# FPSInterface.net
KiCad netlist of a schematic drawn in Altium Designer
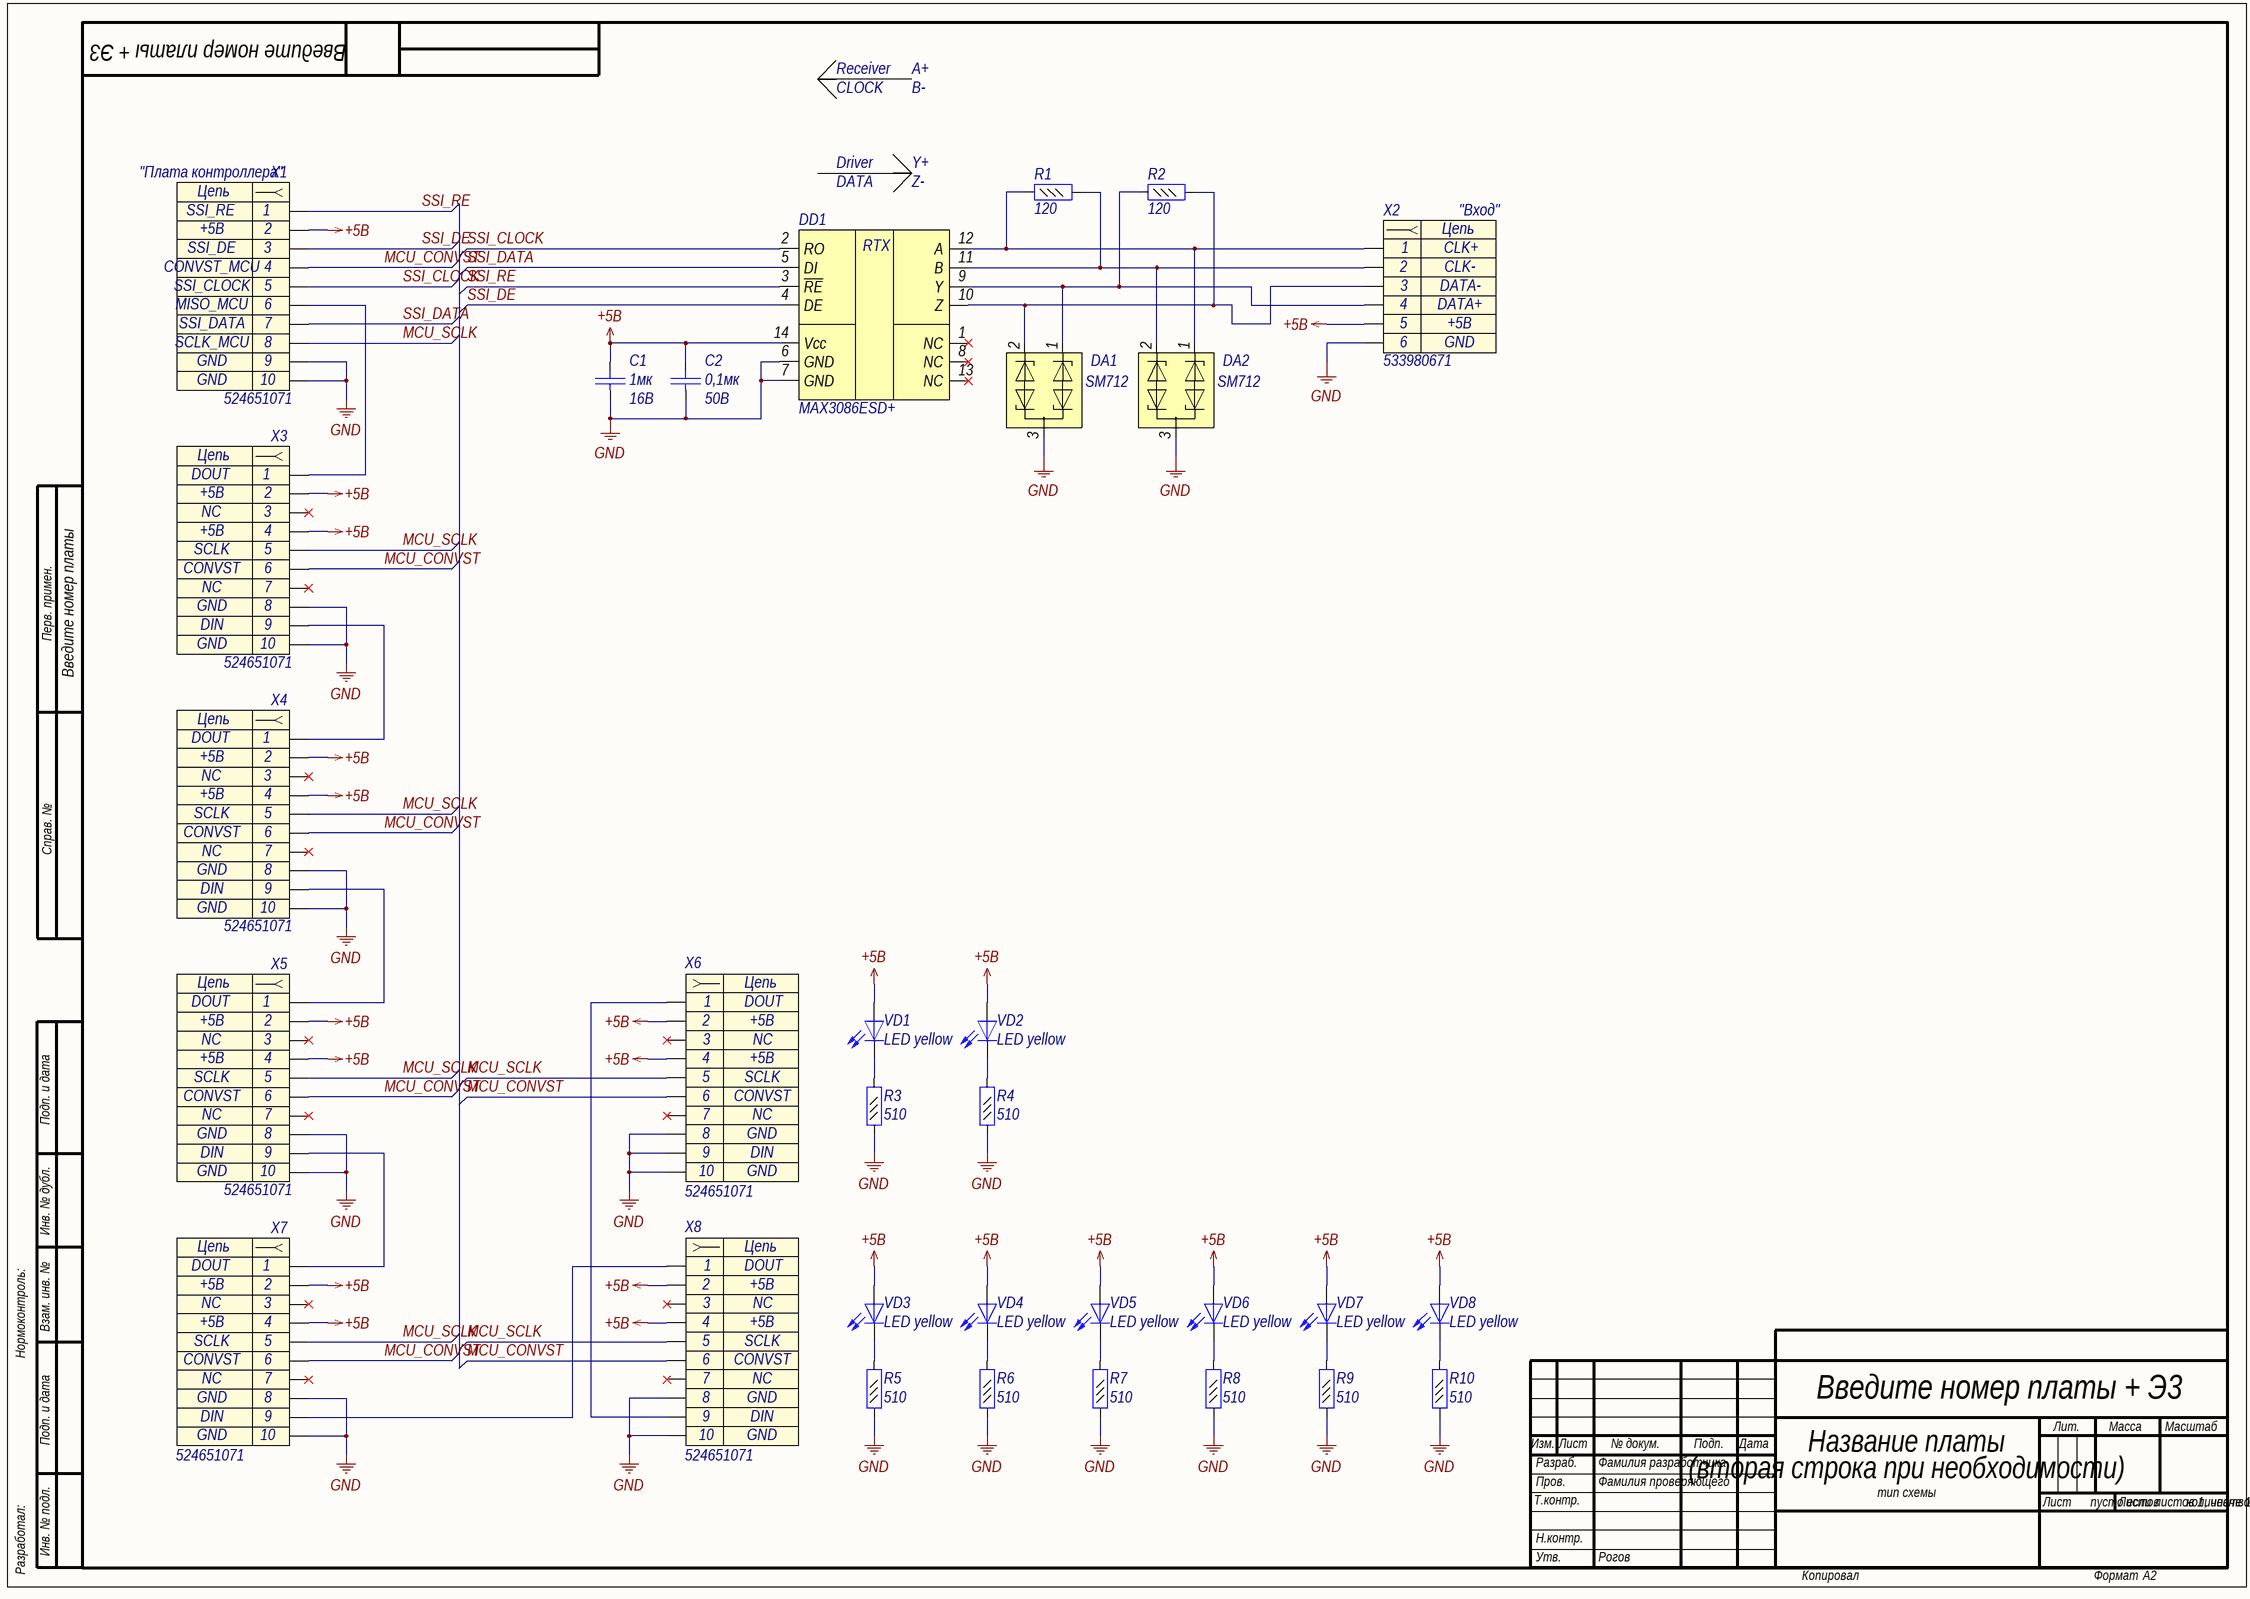
[diagram p0: FPSInterface.SchDoc]

(export (version "E")
  (design (tool "Eeschema 10.0.6"))
  (components
    (comp (ref "C1")
      (value "1мк")
      (footprint "C0603")
      (description "Конденсатор")
      (fields
        (field (name "VOLTAGE") "16B")
        (field (name "PART NUMBER") "GRM188R71C105KA12D**")
        (field (name "Comment") "Capacitor")
      )
      (libsource (lib "MOP44") (part "Capacitor"))
    )
    (comp (ref "C2")
      (value "0,1мк")
      (footprint "C0402")
      (description "Конденсатор")
      (fields
        (field (name "VOLTAGE") "50В")
        (field (name "PART NUMBER") "GRM155R71H104KE14D")
        (field (name "Comment") "Capacitor")
      )
      (libsource (lib "MOP44") (part "Capacitor"))
    )
    (comp (ref "DA1")
      (value "SM712")
      (footprint "SOT23-3")
      (description "TVS")
      (fields (field (name "PART NUMBER") "SM712.TCT"))
      (libsource (lib "MOP44") (part "SM712"))
    )
    (comp (ref "DA2")
      (value "SM712")
      (footprint "SOT23-3")
      (description "TVS")
      (fields (field (name "PART NUMBER") "SM712.TCT"))
      (libsource (lib "MOP44") (part "SM712"))
    )
    (comp (ref "DD1")
      (value "~")
      (footprint "SO14")
      (description "Fail-Safe, High-Speed (10Mbps),  Slew-Rate-Limited RS-485/RS-422 Transceivers")
      (fields (field (name "PART NUMBER") "MAX3086ESD+"))
      (libsource (lib "MOP44") (part "MAX3086"))
    )
    (comp (ref "R1")
      (value "120")
      (footprint "R0402")
      (description "Резистор")
      (fields (field (name "PART NUMBER") "RC0402FR-07120RL") (field (name "POWER") "0,062Вт"))
      (libsource (lib "") (part "Resistor_0,062Вт_1"))
    )
    (comp (ref "R2")
      (value "120")
      (footprint "R0402")
      (description "Резистор")
      (fields (field (name "PART NUMBER") "RC0402FR-07120RL") (field (name "POWER") "0,062Вт"))
      (libsource (lib "") (part "Resistor_0,062Вт_1"))
    )
    (comp (ref "R3")
      (value "510")
      (footprint "R0402")
      (description "Резистор")
      (fields (field (name "PART NUMBER") "RC0402FR-07510RL") (field (name "POWER") "0,062Вт"))
      (libsource (lib "MOP44") (part "Resistor_0,062Вт"))
    )
    (comp (ref "R4")
      (value "510")
      (footprint "R0402")
      (description "Резистор")
      (fields (field (name "PART NUMBER") "RC0402FR-07510RL") (field (name "POWER") "0,062Вт"))
      (libsource (lib "MOP44") (part "Resistor_0,062Вт"))
    )
    (comp (ref "R5")
      (value "510")
      (footprint "R0402")
      (description "Резистор")
      (fields (field (name "PART NUMBER") "RC0402FR-07510RL") (field (name "POWER") "0,062Вт"))
      (libsource (lib "MOP44") (part "Resistor_0,062Вт"))
    )
    (comp (ref "R6")
      (value "510")
      (footprint "R0402")
      (description "Резистор")
      (fields (field (name "PART NUMBER") "RC0402FR-07510RL") (field (name "POWER") "0,062Вт"))
      (libsource (lib "MOP44") (part "Resistor_0,062Вт"))
    )
    (comp (ref "R7")
      (value "510")
      (footprint "R0402")
      (description "Резистор")
      (fields (field (name "PART NUMBER") "RC0402FR-07510RL") (field (name "POWER") "0,062Вт"))
      (libsource (lib "MOP44") (part "Resistor_0,062Вт"))
    )
    (comp (ref "R8")
      (value "510")
      (footprint "R0402")
      (description "Резистор")
      (fields (field (name "PART NUMBER") "RC0402FR-07510RL") (field (name "POWER") "0,062Вт"))
      (libsource (lib "MOP44") (part "Resistor_0,062Вт"))
    )
    (comp (ref "R9")
      (value "510")
      (footprint "R0402")
      (description "Резистор")
      (fields (field (name "PART NUMBER") "RC0402FR-07510RL") (field (name "POWER") "0,062Вт"))
      (libsource (lib "MOP44") (part "Resistor_0,062Вт"))
    )
    (comp (ref "R10")
      (value "510")
      (footprint "R0402")
      (description "Резистор")
      (fields (field (name "PART NUMBER") "RC0402FR-07510RL") (field (name "POWER") "0,062Вт"))
      (libsource (lib "MOP44") (part "Resistor_0,062Вт"))
    )
    (comp (ref "VD1")
      (value "LED")
      (footprint "L_0402_YELLOW")
      (description "Светодиод")
      (fields (field (name "PART NAME") "LED yellow") (field (name "PART NUMBER") "KPHHS-1005SYCK"))
      (libsource (lib "MOP44") (part "LED"))
    )
    (comp (ref "VD2")
      (value "LED")
      (footprint "L_0402_YELLOW")
      (description "Светодиод")
      (fields (field (name "PART NAME") "LED yellow") (field (name "PART NUMBER") "KPHHS-1005SYCK"))
      (libsource (lib "MOP44") (part "LED"))
    )
    (comp (ref "VD3")
      (value "LED")
      (footprint "L_0402_YELLOW")
      (description "Светодиод")
      (fields (field (name "PART NAME") "LED yellow") (field (name "PART NUMBER") "KPHHS-1005SYCK"))
      (libsource (lib "MOP44") (part "LED"))
    )
    (comp (ref "VD4")
      (value "LED")
      (footprint "L_0402_YELLOW")
      (description "Светодиод")
      (fields (field (name "PART NAME") "LED yellow") (field (name "PART NUMBER") "KPHHS-1005SYCK"))
      (libsource (lib "MOP44") (part "LED"))
    )
    (comp (ref "VD5")
      (value "LED")
      (footprint "L_0402_YELLOW")
      (description "Светодиод")
      (fields (field (name "PART NAME") "LED yellow") (field (name "PART NUMBER") "KPHHS-1005SYCK"))
      (libsource (lib "MOP44") (part "LED"))
    )
    (comp (ref "VD6")
      (value "LED")
      (footprint "L_0402_YELLOW")
      (description "Светодиод")
      (fields (field (name "PART NAME") "LED yellow") (field (name "PART NUMBER") "KPHHS-1005SYCK"))
      (libsource (lib "MOP44") (part "LED"))
    )
    (comp (ref "VD7")
      (value "LED")
      (footprint "L_0402_YELLOW")
      (description "Светодиод")
      (fields (field (name "PART NAME") "LED yellow") (field (name "PART NUMBER") "KPHHS-1005SYCK"))
      (libsource (lib "MOP44") (part "LED"))
    )
    (comp (ref "VD8")
      (value "LED")
      (footprint "L_0402_YELLOW")
      (description "Светодиод")
      (fields (field (name "PART NAME") "LED yellow") (field (name "PART NUMBER") "KPHHS-1005SYCK"))
      (libsource (lib "MOP44") (part "LED"))
    )
    (comp (ref "X1")
      (value "\"Плата контроллера\"")
      (footprint "SlimStack-10pin-vert-sct")
      (description "Разъем - 10 конт. розетка")
      (fields (field (name "PART NUMBER") "524651071"))
      (libsource (lib "") (part "Header_10_sct_1"))
    )
    (comp (ref "X2")
      (value "\"Вход\"")
      (footprint "MOLEX_533980671")
      (description "Разъем - 6 конт. розетка")
      (fields (field (name "PART NUMBER") "533980671"))
      (libsource (lib "MOP44") (part "Header_6_sct"))
    )
    (comp (ref "X3")
      (value "Header_10_sct")
      (footprint "SlimStack-10pin-vert-sct")
      (description "Разъем - 10 конт. розетка")
      (fields (field (name "PART NUMBER") "524651071"))
      (libsource (lib "") (part "Header_10_sct_1"))
    )
    (comp (ref "X4")
      (value "Header_10_sct")
      (footprint "SlimStack-10pin-vert-sct")
      (description "Разъем - 10 конт. розетка")
      (fields (field (name "PART NUMBER") "524651071"))
      (libsource (lib "") (part "Header_10_sct_1"))
    )
    (comp (ref "X5")
      (value "Header_10_sct")
      (footprint "SlimStack-10pin-vert-sct")
      (description "Разъем - 10 конт. розетка")
      (fields (field (name "PART NUMBER") "524651071"))
      (libsource (lib "") (part "Header_10_sct_1"))
    )
    (comp (ref "X6")
      (value "Header_10_sct")
      (footprint "SlimStack-10pin-vert-sct")
      (description "Разъем - 10 конт. розетка")
      (fields (field (name "PART NUMBER") "524651071"))
      (libsource (lib "MOP44") (part "Header_10_sct"))
    )
    (comp (ref "X7")
      (value "Header_10_sct")
      (footprint "SlimStack-10pin-vert-sct")
      (description "Разъем - 10 конт. розетка")
      (fields (field (name "PART NUMBER") "524651071"))
      (libsource (lib "") (part "Header_10_sct_1"))
    )
    (comp (ref "X8")
      (value "Header_10_sct")
      (footprint "SlimStack-10pin-vert-sct")
      (description "Разъем - 10 конт. розетка")
      (fields (field (name "PART NUMBER") "524651071"))
      (libsource (lib "MOP44") (part "Header_10_sct"))
    )
  )
  (nets
    (net (code "1") (name "+5B") (class "Default")
      (node (ref "C1") (pin "2") (pinfunction "2_2") (pintype "passive"))
      (node (ref "C2") (pin "2") (pinfunction "2_2") (pintype "passive"))
      (node (ref "DD1") (pin "14") (pinfunction "Vcc_14") (pintype "passive"))
      (node (ref "VD1") (pin "2") (pinfunction "A_2") (pintype "passive"))
      (node (ref "VD2") (pin "2") (pinfunction "A_2") (pintype "passive"))
      (node (ref "VD3") (pin "2") (pinfunction "A_2") (pintype "passive"))
      (node (ref "VD4") (pin "2") (pinfunction "A_2") (pintype "passive"))
      (node (ref "VD5") (pin "2") (pinfunction "A_2") (pintype "passive"))
      (node (ref "VD6") (pin "2") (pinfunction "A_2") (pintype "passive"))
      (node (ref "VD7") (pin "2") (pinfunction "A_2") (pintype "passive"))
      (node (ref "VD8") (pin "2") (pinfunction "A_2") (pintype "passive"))
      (node (ref "X1") (pin "2") (pinfunction "2_2") (pintype "passive"))
      (node (ref "X2") (pin "5") (pinfunction "5_5") (pintype "passive"))
      (node (ref "X3") (pin "2") (pinfunction "2_2") (pintype "passive"))
      (node (ref "X3") (pin "4") (pinfunction "4_4") (pintype "passive"))
      (node (ref "X4") (pin "2") (pinfunction "2_2") (pintype "passive"))
      (node (ref "X4") (pin "4") (pinfunction "4_4") (pintype "passive"))
      (node (ref "X5") (pin "2") (pinfunction "2_2") (pintype "passive"))
      (node (ref "X5") (pin "4") (pinfunction "4_4") (pintype "passive"))
      (node (ref "X6") (pin "2") (pinfunction "2_2") (pintype "passive"))
      (node (ref "X6") (pin "4") (pinfunction "4_4") (pintype "passive"))
      (node (ref "X7") (pin "2") (pinfunction "2_2") (pintype "passive"))
      (node (ref "X7") (pin "4") (pinfunction "4_4") (pintype "passive"))
      (node (ref "X8") (pin "2") (pinfunction "2_2") (pintype "passive"))
      (node (ref "X8") (pin "4") (pinfunction "4_4") (pintype "passive"))
    )
    (net (code "2") (name "/MCU_CONVST") (class "Default")
      (node (ref "X1") (pin "4") (pinfunction "4_4") (pintype "passive"))
      (node (ref "X3") (pin "6") (pinfunction "6_6") (pintype "passive"))
      (node (ref "X4") (pin "6") (pinfunction "6_6") (pintype "passive"))
      (node (ref "X5") (pin "6") (pinfunction "6_6") (pintype "passive"))
      (node (ref "X6") (pin "6") (pinfunction "6_6") (pintype "passive"))
      (node (ref "X7") (pin "6") (pinfunction "6_6") (pintype "passive"))
      (node (ref "X8") (pin "6") (pinfunction "6_6") (pintype "passive"))
    )
    (net (code "3") (name "/MCU_SCLK") (class "Default")
      (node (ref "X1") (pin "8") (pinfunction "8_8") (pintype "passive"))
      (node (ref "X3") (pin "5") (pinfunction "5_5") (pintype "passive"))
      (node (ref "X4") (pin "5") (pinfunction "5_5") (pintype "passive"))
      (node (ref "X5") (pin "5") (pinfunction "5_5") (pintype "passive"))
      (node (ref "X6") (pin "5") (pinfunction "5_5") (pintype "passive"))
      (node (ref "X7") (pin "5") (pinfunction "5_5") (pintype "passive"))
      (node (ref "X8") (pin "5") (pinfunction "5_5") (pintype "passive"))
    )
    (net (code "4") (name "/SSI_CLOCK") (class "Default")
      (node (ref "DD1") (pin "2") (pinfunction "RO_2") (pintype "passive"))
      (node (ref "X1") (pin "5") (pinfunction "5_5") (pintype "passive"))
    )
    (net (code "5") (name "/SSI_DATA") (class "Default")
      (node (ref "DD1") (pin "5") (pinfunction "DI_5") (pintype "passive"))
      (node (ref "X1") (pin "7") (pinfunction "7_7") (pintype "passive"))
    )
    (net (code "6") (name "/SSI_DE") (class "Default")
      (node (ref "DD1") (pin "4") (pinfunction "DE_4") (pintype "passive"))
      (node (ref "X1") (pin "3") (pinfunction "3_3") (pintype "passive"))
    )
    (net (code "7") (name "/SSI_RE") (class "Default")
      (node (ref "DD1") (pin "3") (pinfunction "~{RE}_3") (pintype "passive"))
      (node (ref "X1") (pin "1") (pinfunction "1_1") (pintype "passive"))
    )
    (net (code "8") (name "GND") (class "Default")
      (node (ref "C1") (pin "1") (pinfunction "1_1") (pintype "passive"))
      (node (ref "C2") (pin "1") (pinfunction "1_1") (pintype "passive"))
      (node (ref "DA1") (pin "3") (pintype "passive"))
      (node (ref "DA2") (pin "3") (pintype "passive"))
      (node (ref "DD1") (pin "6") (pinfunction "GND_6") (pintype "passive"))
      (node (ref "DD1") (pin "7") (pinfunction "GND_7") (pintype "passive"))
      (node (ref "R10") (pin "1") (pinfunction "1_1") (pintype "passive"))
      (node (ref "R3") (pin "1") (pinfunction "1_1") (pintype "passive"))
      (node (ref "R4") (pin "1") (pinfunction "1_1") (pintype "passive"))
      (node (ref "R5") (pin "1") (pinfunction "1_1") (pintype "passive"))
      (node (ref "R6") (pin "1") (pinfunction "1_1") (pintype "passive"))
      (node (ref "R7") (pin "1") (pinfunction "1_1") (pintype "passive"))
      (node (ref "R8") (pin "1") (pinfunction "1_1") (pintype "passive"))
      (node (ref "R9") (pin "1") (pinfunction "1_1") (pintype "passive"))
      (node (ref "X1") (pin "10") (pinfunction "10_10") (pintype "passive"))
      (node (ref "X1") (pin "9") (pinfunction "9_9") (pintype "passive"))
      (node (ref "X2") (pin "6") (pinfunction "6_6") (pintype "passive"))
      (node (ref "X3") (pin "10") (pinfunction "10_10") (pintype "passive"))
      (node (ref "X3") (pin "8") (pinfunction "8_8") (pintype "passive"))
      (node (ref "X4") (pin "10") (pinfunction "10_10") (pintype "passive"))
      (node (ref "X4") (pin "8") (pinfunction "8_8") (pintype "passive"))
      (node (ref "X5") (pin "10") (pinfunction "10_10") (pintype "passive"))
      (node (ref "X5") (pin "8") (pinfunction "8_8") (pintype "passive"))
      (node (ref "X6") (pin "10") (pinfunction "10_10") (pintype "passive"))
      (node (ref "X6") (pin "8") (pinfunction "8_8") (pintype "passive"))
      (node (ref "X6") (pin "9") (pinfunction "9_9") (pintype "passive"))
      (node (ref "X7") (pin "10") (pinfunction "10_10") (pintype "passive"))
      (node (ref "X7") (pin "8") (pinfunction "8_8") (pintype "passive"))
      (node (ref "X8") (pin "10") (pinfunction "10_10") (pintype "passive"))
      (node (ref "X8") (pin "8") (pinfunction "8_8") (pintype "passive"))
    )
    (net (code "9") (name "Net-(DA1-1)") (class "Default")
      (node (ref "DA1") (pin "2") (pinfunction "1_2") (pintype "passive"))
      (node (ref "DD1") (pin "10") (pinfunction "Z_10") (pintype "passive"))
      (node (ref "R2") (pin "2") (pinfunction "2_2") (pintype "passive"))
      (node (ref "X2") (pin "3") (pinfunction "3_3") (pintype "passive"))
    )
    (net (code "10") (name "Net-(DA2-1)") (class "Default")
      (node (ref "DA2") (pin "2") (pinfunction "1_2") (pintype "passive"))
      (node (ref "DD1") (pin "11") (pinfunction "B_11") (pintype "passive"))
      (node (ref "R1") (pin "2") (pinfunction "2_2") (pintype "passive"))
      (node (ref "X2") (pin "2") (pinfunction "2_2") (pintype "passive"))
    )
    (net (code "11") (name "Net-(DD1-A)") (class "Default")
      (node (ref "DA2") (pin "1") (pintype "passive"))
      (node (ref "DD1") (pin "12") (pinfunction "A_12") (pintype "passive"))
      (node (ref "R1") (pin "1") (pinfunction "1_1") (pintype "passive"))
      (node (ref "X2") (pin "1") (pinfunction "1_1") (pintype "passive"))
    )
    (net (code "12") (name "Net-(DD1-Y)") (class "Default")
      (node (ref "DA1") (pin "1") (pintype "passive"))
      (node (ref "DD1") (pin "9") (pinfunction "Y_9") (pintype "passive"))
      (node (ref "R2") (pin "1") (pinfunction "1_1") (pintype "passive"))
      (node (ref "X2") (pin "4") (pinfunction "4_4") (pintype "passive"))
    )
    (net (code "13") (name "Net-(VD1-K)") (class "Default")
      (node (ref "R3") (pin "2") (pinfunction "2_2") (pintype "passive"))
      (node (ref "VD1") (pin "1") (pinfunction "K_1") (pintype "passive"))
    )
    (net (code "14") (name "Net-(VD2-K)") (class "Default")
      (node (ref "R4") (pin "2") (pinfunction "2_2") (pintype "passive"))
      (node (ref "VD2") (pin "1") (pinfunction "K_1") (pintype "passive"))
    )
    (net (code "15") (name "Net-(VD3-K)") (class "Default")
      (node (ref "R5") (pin "2") (pinfunction "2_2") (pintype "passive"))
      (node (ref "VD3") (pin "1") (pinfunction "K_1") (pintype "passive"))
    )
    (net (code "16") (name "Net-(VD4-K)") (class "Default")
      (node (ref "R6") (pin "2") (pinfunction "2_2") (pintype "passive"))
      (node (ref "VD4") (pin "1") (pinfunction "K_1") (pintype "passive"))
    )
    (net (code "17") (name "Net-(VD5-K)") (class "Default")
      (node (ref "R7") (pin "2") (pinfunction "2_2") (pintype "passive"))
      (node (ref "VD5") (pin "1") (pinfunction "K_1") (pintype "passive"))
    )
    (net (code "18") (name "Net-(VD6-K)") (class "Default")
      (node (ref "R8") (pin "2") (pinfunction "2_2") (pintype "passive"))
      (node (ref "VD6") (pin "1") (pinfunction "K_1") (pintype "passive"))
    )
    (net (code "19") (name "Net-(VD7-K)") (class "Default")
      (node (ref "R9") (pin "2") (pinfunction "2_2") (pintype "passive"))
      (node (ref "VD7") (pin "1") (pinfunction "K_1") (pintype "passive"))
    )
    (net (code "20") (name "Net-(VD8-K)") (class "Default")
      (node (ref "R10") (pin "2") (pinfunction "2_2") (pintype "passive"))
      (node (ref "VD8") (pin "1") (pinfunction "K_1") (pintype "passive"))
    )
    (net (code "21") (name "Net-(X1-Pad6)") (class "Default")
      (node (ref "X1") (pin "6") (pinfunction "6_6") (pintype "passive"))
      (node (ref "X3") (pin "1") (pinfunction "1_1") (pintype "passive"))
    )
    (net (code "22") (name "Net-(X3-Pad9)") (class "Default")
      (node (ref "X3") (pin "9") (pinfunction "9_9") (pintype "passive"))
      (node (ref "X4") (pin "1") (pinfunction "1_1") (pintype "passive"))
    )
    (net (code "23") (name "Net-(X4-Pad9)") (class "Default")
      (node (ref "X4") (pin "9") (pinfunction "9_9") (pintype "passive"))
      (node (ref "X5") (pin "1") (pinfunction "1_1") (pintype "passive"))
    )
    (net (code "24") (name "Net-(X5-Pad9)") (class "Default")
      (node (ref "X5") (pin "9") (pinfunction "9_9") (pintype "passive"))
      (node (ref "X7") (pin "1") (pinfunction "1_1") (pintype "passive"))
    )
    (net (code "25") (name "Net-(X6-Pad1)") (class "Default")
      (node (ref "X6") (pin "1") (pinfunction "1_1") (pintype "passive"))
      (node (ref "X8") (pin "9") (pinfunction "9_9") (pintype "passive"))
    )
    (net (code "26") (name "Net-(X7-Pad9)") (class "Default")
      (node (ref "X7") (pin "9") (pinfunction "9_9") (pintype "passive"))
      (node (ref "X8") (pin "1") (pinfunction "1_1") (pintype "passive"))
    )
    (net (code "27") (name "unconnected-(DD1-NC-Pad1)") (class "Default")
      (node (ref "DD1") (pin "1") (pinfunction "NC_1") (pintype "passive+no_connect"))
    )
    (net (code "28") (name "unconnected-(DD1-NC-Pad8)") (class "Default")
      (node (ref "DD1") (pin "8") (pinfunction "NC_8") (pintype "passive+no_connect"))
    )
    (net (code "29") (name "unconnected-(DD1-NC-Pad13)") (class "Default")
      (node (ref "DD1") (pin "13") (pinfunction "NC_13") (pintype "passive+no_connect"))
    )
    (net (code "30") (name "unconnected-(X3-Pad3)") (class "Default")
      (node (ref "X3") (pin "3") (pinfunction "3_3") (pintype "passive+no_connect"))
    )
    (net (code "31") (name "unconnected-(X3-Pad7)") (class "Default")
      (node (ref "X3") (pin "7") (pinfunction "7_7") (pintype "passive+no_connect"))
    )
    (net (code "32") (name "unconnected-(X4-Pad3)") (class "Default")
      (node (ref "X4") (pin "3") (pinfunction "3_3") (pintype "passive+no_connect"))
    )
    (net (code "33") (name "unconnected-(X4-Pad7)") (class "Default")
      (node (ref "X4") (pin "7") (pinfunction "7_7") (pintype "passive+no_connect"))
    )
    (net (code "34") (name "unconnected-(X5-Pad3)") (class "Default")
      (node (ref "X5") (pin "3") (pinfunction "3_3") (pintype "passive+no_connect"))
    )
    (net (code "35") (name "unconnected-(X5-Pad7)") (class "Default")
      (node (ref "X5") (pin "7") (pinfunction "7_7") (pintype "passive+no_connect"))
    )
    (net (code "36") (name "unconnected-(X6-Pad3)") (class "Default")
      (node (ref "X6") (pin "3") (pinfunction "3_3") (pintype "passive+no_connect"))
    )
    (net (code "37") (name "unconnected-(X6-Pad7)") (class "Default")
      (node (ref "X6") (pin "7") (pinfunction "7_7") (pintype "passive+no_connect"))
    )
    (net (code "38") (name "unconnected-(X7-Pad3)") (class "Default")
      (node (ref "X7") (pin "3") (pinfunction "3_3") (pintype "passive+no_connect"))
    )
    (net (code "39") (name "unconnected-(X7-Pad7)") (class "Default")
      (node (ref "X7") (pin "7") (pinfunction "7_7") (pintype "passive+no_connect"))
    )
    (net (code "40") (name "unconnected-(X8-Pad3)") (class "Default")
      (node (ref "X8") (pin "3") (pinfunction "3_3") (pintype "passive+no_connect"))
    )
    (net (code "41") (name "unconnected-(X8-Pad7)") (class "Default")
      (node (ref "X8") (pin "7") (pinfunction "7_7") (pintype "passive+no_connect"))
    )
  )
)
